# board.net
KiCad netlist of a schematic drawn in EAGLE
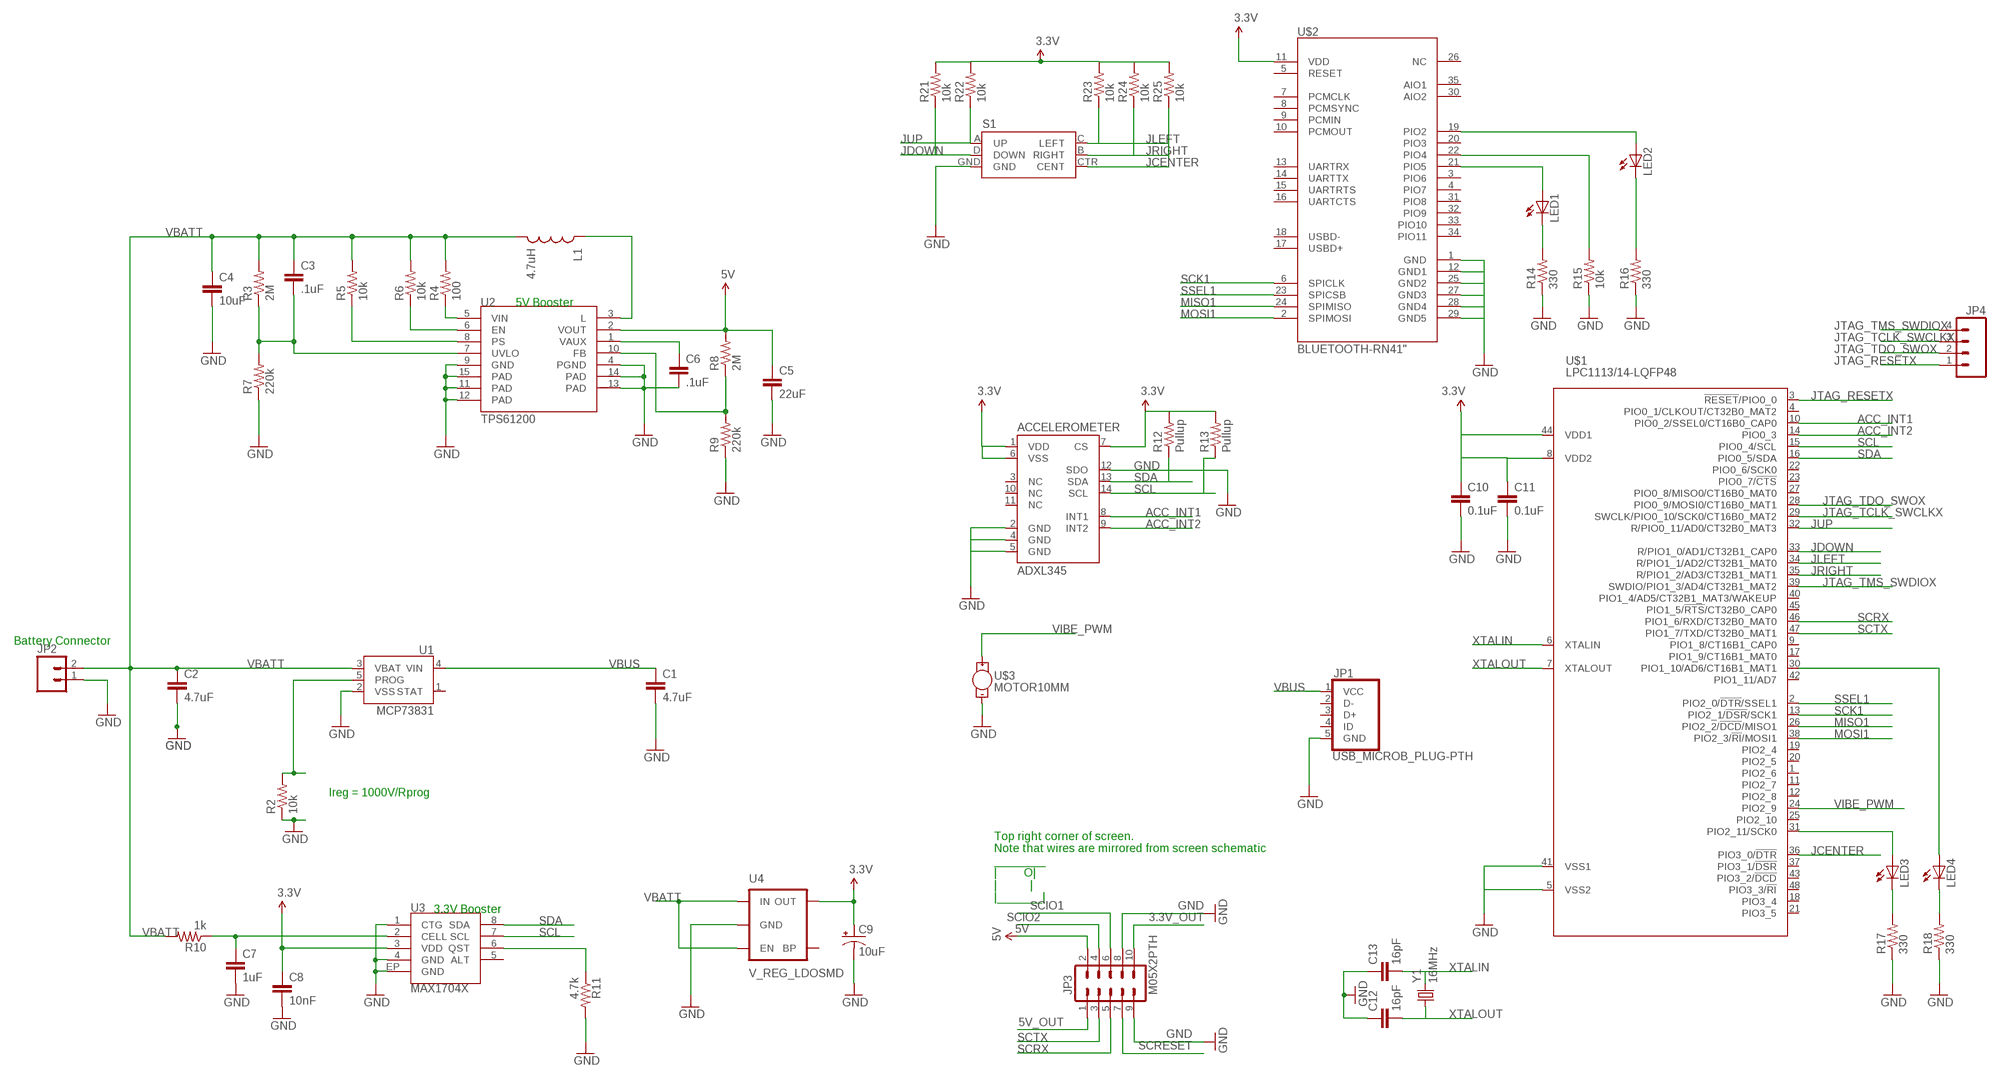
[diagram p0: schematic, sheet 1]

(export (version "E")
  (design (tool "Eeschema 10.0.6"))
  (components
    (comp (ref "ACCELEROMETER")
      (value "ADXL345")
      (footprint "eagle-import:LGA14")
      (libsource (lib "eagle-import") (part "ADXL345"))
    )
    (comp (ref "C1")
      (value "4.7uF")
      (footprint "eagle-import:0402-CAP")
      (libsource (lib "eagle-import") (part "CAP0402-CAP"))
    )
    (comp (ref "C2")
      (value "4.7uF")
      (footprint "eagle-import:0402-CAP")
      (libsource (lib "eagle-import") (part "CAP0402-CAP"))
    )
    (comp (ref "C3")
      (value ".1uF")
      (footprint "eagle-import:0402-CAP")
      (libsource (lib "eagle-import") (part "CAP0402-CAP"))
    )
    (comp (ref "C4")
      (value "10uF")
      (footprint "eagle-import:0402-CAP")
      (libsource (lib "eagle-import") (part "CAP0402-CAP"))
    )
    (comp (ref "C5")
      (value "22uF")
      (footprint "eagle-import:0402-CAP")
      (libsource (lib "eagle-import") (part "CAP0402-CAP"))
    )
    (comp (ref "C6")
      (value ".1uF")
      (footprint "eagle-import:0402-CAP")
      (libsource (lib "eagle-import") (part "CAP0402-CAP"))
    )
    (comp (ref "C7")
      (value "1uF")
      (footprint "eagle-import:0402-CAP")
      (libsource (lib "eagle-import") (part "CAP0402-CAP"))
    )
    (comp (ref "C8")
      (value "10nF")
      (footprint "eagle-import:0402-CAP")
      (libsource (lib "eagle-import") (part "CAP0402-CAP"))
    )
    (comp (ref "C9")
      (value "10uF")
      (footprint "eagle-import:EIA3216")
      (libsource (lib "eagle-import") (part "10UF-TANT"))
    )
    (comp (ref "C10")
      (value "0.1uF")
      (footprint "eagle-import:0402-CAP")
      (libsource (lib "eagle-import") (part ".1UF-CER"))
    )
    (comp (ref "C11")
      (value "0.1uF")
      (footprint "eagle-import:0402-CAP")
      (libsource (lib "eagle-import") (part ".1UF-CER"))
    )
    (comp (ref "C12")
      (value "16pF")
      (footprint "eagle-import:0402-CAP")
      (libsource (lib "eagle-import") (part "CAP0402-CAP"))
    )
    (comp (ref "C13")
      (value "16pF")
      (footprint "eagle-import:0402-CAP")
      (libsource (lib "eagle-import") (part "CAP0402-CAP"))
    )
    (comp (ref "JP1")
      (value "USB_MICROB_PLUG-PTH")
      (footprint "eagle-import:MICRO-B-RA-TH")
      (libsource (lib "eagle-import") (part "USB_MICROB_PLUG-PTH"))
    )
    (comp (ref "JP2")
      (value "M02-JST-2-PTH-NO_SILK")
      (footprint "eagle-import:JST-2-PTH-NS")
      (libsource (lib "eagle-import") (part "M02-JST-2-PTH-NO_SILK"))
    )
    (comp (ref "JP3")
      (value "M05X2PTH")
      (footprint "eagle-import:AVR_ICSP")
      (libsource (lib "eagle-import") (part "M05X2PTH"))
    )
    (comp (ref "JP4")
      (value "M04POLAR")
      (footprint "eagle-import:MOLEX-1X4")
      (libsource (lib "eagle-import") (part "M04POLAR"))
    )
    (comp (ref "L1")
      (value "4.7uH")
      (footprint "eagle-import:C0402")
      (libsource (lib "eagle-import") (part "INDUCTOR0402"))
    )
    (comp (ref "LED1")
      (value "LED0603")
      (footprint "eagle-import:LED-0603")
      (libsource (lib "eagle-import") (part "LED0603"))
    )
    (comp (ref "LED2")
      (value "LED0603")
      (footprint "eagle-import:LED-0603")
      (libsource (lib "eagle-import") (part "LED0603"))
    )
    (comp (ref "LED3")
      (value "LED0603")
      (footprint "eagle-import:LED-0603")
      (libsource (lib "eagle-import") (part "LED0603"))
    )
    (comp (ref "LED4")
      (value "LED0603")
      (footprint "eagle-import:LED-0603")
      (libsource (lib "eagle-import") (part "LED0603"))
    )
    (comp (ref "R2")
      (value "10k")
      (footprint "eagle-import:0402-RES")
      (libsource (lib "eagle-import") (part "RESISTOR0402-RES"))
    )
    (comp (ref "R3")
      (value "2M")
      (footprint "eagle-import:0402-RES")
      (libsource (lib "eagle-import") (part "RESISTOR0402-RES"))
    )
    (comp (ref "R4")
      (value "100")
      (footprint "eagle-import:0402-RES")
      (libsource (lib "eagle-import") (part "RESISTOR0402-RES"))
    )
    (comp (ref "R5")
      (value "10k")
      (footprint "eagle-import:0402-RES")
      (libsource (lib "eagle-import") (part "RESISTOR0402-RES"))
    )
    (comp (ref "R6")
      (value "10k")
      (footprint "eagle-import:0402-RES")
      (libsource (lib "eagle-import") (part "RESISTOR0402-RES"))
    )
    (comp (ref "R7")
      (value "220k")
      (footprint "eagle-import:0402-RES")
      (libsource (lib "eagle-import") (part "RESISTOR0402-RES"))
    )
    (comp (ref "R8")
      (value "2M")
      (footprint "eagle-import:0402-RES")
      (libsource (lib "eagle-import") (part "RESISTOR0402-RES"))
    )
    (comp (ref "R9")
      (value "220k")
      (footprint "eagle-import:0402-RES")
      (libsource (lib "eagle-import") (part "RESISTOR0402-RES"))
    )
    (comp (ref "R10")
      (value "1k")
      (footprint "eagle-import:0402-RES")
      (libsource (lib "eagle-import") (part "RESISTOR0402-RES"))
    )
    (comp (ref "R11")
      (value "4.7k")
      (footprint "eagle-import:0402-RES")
      (libsource (lib "eagle-import") (part "RESISTOR0402-RES"))
    )
    (comp (ref "R12")
      (value "Pullup")
      (footprint "eagle-import:0402-RES")
      (libsource (lib "eagle-import") (part "RESISTOR0402-RES"))
    )
    (comp (ref "R13")
      (value "Pullup")
      (footprint "eagle-import:0402-RES")
      (libsource (lib "eagle-import") (part "RESISTOR0402-RES"))
    )
    (comp (ref "R14")
      (value "330")
      (footprint "eagle-import:0402-RES")
      (libsource (lib "eagle-import") (part "RESISTOR0402-RES"))
    )
    (comp (ref "R15")
      (value "10k")
      (footprint "eagle-import:0402-RES")
      (libsource (lib "eagle-import") (part "RESISTOR0402-RES"))
    )
    (comp (ref "R16")
      (value "330")
      (footprint "eagle-import:0402-RES")
      (libsource (lib "eagle-import") (part "RESISTOR0402-RES"))
    )
    (comp (ref "R17")
      (value "330")
      (footprint "eagle-import:0402-RES")
      (libsource (lib "eagle-import") (part "RESISTOR0402-RES"))
    )
    (comp (ref "R18")
      (value "330")
      (footprint "eagle-import:0402-RES")
      (libsource (lib "eagle-import") (part "RESISTOR0402-RES"))
    )
    (comp (ref "R21")
      (value "10k")
      (footprint "eagle-import:0402-RES")
      (libsource (lib "eagle-import") (part "RESISTOR0402-RES"))
    )
    (comp (ref "R22")
      (value "10k")
      (footprint "eagle-import:0402-RES")
      (libsource (lib "eagle-import") (part "RESISTOR0402-RES"))
    )
    (comp (ref "R23")
      (value "10k")
      (footprint "eagle-import:0402-RES")
      (libsource (lib "eagle-import") (part "RESISTOR0402-RES"))
    )
    (comp (ref "R24")
      (value "10k")
      (footprint "eagle-import:0402-RES")
      (libsource (lib "eagle-import") (part "RESISTOR0402-RES"))
    )
    (comp (ref "R25")
      (value "10k")
      (footprint "eagle-import:0402-RES")
      (libsource (lib "eagle-import") (part "RESISTOR0402-RES"))
    )
    (comp (ref "S1")
      (value "JOYSTICK_MINI")
      (footprint "eagle-import:JOYSTICK_MINI")
      (libsource (lib "eagle-import") (part "JOYSTICK_MINI"))
    )
    (comp (ref "U$1")
      (value "LPC1113/14-LQFP48")
      (footprint "eagle-import:LQFP48")
      (libsource (lib "eagle-import") (part "LPC1113/14-LQFP48"))
    )
    (comp (ref "U$2")
      (value "BLUETOOTH-RN41\"")
      (footprint "eagle-import:RN41")
      (libsource (lib "eagle-import") (part "BLUETOOTH-RN41{dblquote}"))
    )
    (comp (ref "U$3")
      (value "MOTOR10MM")
      (footprint "eagle-import:VIBE-MOTOR-10MM")
      (libsource (lib "eagle-import") (part "MOTOR10MM"))
    )
    (comp (ref "U1")
      (value "MCP73831")
      (footprint "eagle-import:SOT23-5")
      (libsource (lib "eagle-import") (part "MCP73831"))
    )
    (comp (ref "U2")
      (value "TPS61200")
      (footprint "eagle-import:QFN-10_PAD")
      (libsource (lib "eagle-import") (part "TPS61200"))
    )
    (comp (ref "U3")
      (value "MAX1704X")
      (footprint "eagle-import:TDFN-8")
      (libsource (lib "eagle-import") (part "MAX1704X"))
    )
    (comp (ref "U4")
      (value "V_REG_LDOSMD")
      (footprint "eagle-import:SOT23-5")
      (libsource (lib "eagle-import") (part "V_REG_LDOSMD"))
    )
    (comp (ref "Y1")
      (value "16MHz")
      (footprint "eagle-import:CRYSTAL-SMD-5X3")
      (libsource (lib "eagle-import") (part "CRYSTAL5X3"))
    )
  )
  (nets
    (net (code "1") (name "/3.3V_OUT") (class "Default")
      (node (ref "JP3") (pin "10") (pinfunction "10_10") (pintype "passive"))
    )
    (net (code "2") (name "/5V_OUT") (class "Default")
      (node (ref "JP3") (pin "1") (pinfunction "1_1") (pintype "passive"))
    )
    (net (code "3") (name "/ACC_INT1") (class "Default")
      (node (ref "ACCELEROMETER") (pin "8") (pinfunction "INT1_8") (pintype "bidirectional"))
      (node (ref "U$1") (pin "10") (pinfunction "PIO0_2/SSEL0/CT16B0_CAP0_10") (pintype "bidirectional"))
    )
    (net (code "4") (name "/ACC_INT2") (class "Default")
      (node (ref "ACCELEROMETER") (pin "9") (pinfunction "INT2_9") (pintype "bidirectional"))
      (node (ref "U$1") (pin "14") (pinfunction "PIO0_3_14") (pintype "bidirectional"))
    )
    (net (code "5") (name "/JCENTER") (class "Default")
      (node (ref "R25") (pin "1") (pinfunction "1_1") (pintype "passive"))
      (node (ref "S1") (pin "CTR") (pinfunction "CENT_CTR") (pintype "bidirectional"))
      (node (ref "U$1") (pin "36") (pinfunction "PIO3_0/~{DTR}_36") (pintype "bidirectional"))
    )
    (net (code "6") (name "/JDOWN") (class "Default")
      (node (ref "R21") (pin "1") (pinfunction "1_1") (pintype "passive"))
      (node (ref "S1") (pin "D") (pinfunction "DOWN_D") (pintype "bidirectional"))
      (node (ref "U$1") (pin "33") (pinfunction "R/PIO1_0/AD1/CT32B1_CAP0_33") (pintype "bidirectional"))
    )
    (net (code "7") (name "/JLEFT") (class "Default")
      (node (ref "R23") (pin "1") (pinfunction "1_1") (pintype "passive"))
      (node (ref "S1") (pin "C") (pinfunction "LEFT_C") (pintype "bidirectional"))
      (node (ref "U$1") (pin "34") (pinfunction "R/PIO1_1/AD2/CT32B1_MAT0_34") (pintype "bidirectional"))
    )
    (net (code "8") (name "/JRIGHT") (class "Default")
      (node (ref "R24") (pin "1") (pinfunction "1_1") (pintype "passive"))
      (node (ref "S1") (pin "B") (pinfunction "RIGHT_B") (pintype "bidirectional"))
      (node (ref "U$1") (pin "35") (pinfunction "R/PIO1_2/AD3/CT32B1_MAT1_35") (pintype "bidirectional"))
    )
    (net (code "9") (name "/JTAG_RESETX") (class "Default")
      (node (ref "JP4") (pin "1") (pinfunction "1_1") (pintype "passive"))
      (node (ref "U$1") (pin "3") (pinfunction "~{RESET}/PIO0_0_3") (pintype "bidirectional"))
    )
    (net (code "10") (name "/JTAG_TCLK_SWCLKX") (class "Default")
      (node (ref "JP4") (pin "3") (pinfunction "3_3") (pintype "passive"))
      (node (ref "U$1") (pin "29") (pinfunction "SWCLK/PIO0_10/SCK0/CT16B0_MAT2_29") (pintype "bidirectional"))
    )
    (net (code "11") (name "/JTAG_TDO_SWOX") (class "Default")
      (node (ref "JP4") (pin "2") (pinfunction "2_2") (pintype "passive"))
      (node (ref "U$1") (pin "28") (pinfunction "PIO0_9/MOSI0/CT16B0_MAT1_28") (pintype "bidirectional"))
    )
    (net (code "12") (name "/JTAG_TMS_SWDIOX") (class "Default")
      (node (ref "JP4") (pin "4") (pinfunction "4_4") (pintype "passive"))
      (node (ref "U$1") (pin "39") (pinfunction "SWDIO/PIO1_3/AD4/CT32B1_MAT2_39") (pintype "bidirectional"))
    )
    (net (code "13") (name "/JUP") (class "Default")
      (node (ref "R22") (pin "1") (pinfunction "1_1") (pintype "passive"))
      (node (ref "S1") (pin "A") (pinfunction "UP_A") (pintype "bidirectional"))
      (node (ref "U$1") (pin "32") (pinfunction "R/PIO0_11/AD0/CT32B0_MAT3_32") (pintype "bidirectional"))
    )
    (net (code "14") (name "/MISO1") (class "Default")
      (node (ref "U$1") (pin "26") (pinfunction "PIO2_2/~{DCD}/MISO1_26") (pintype "bidirectional"))
      (node (ref "U$2") (pin "24") (pinfunction "SPIMISO_24") (pintype "bidirectional"))
    )
    (net (code "15") (name "/MOSI1") (class "Default")
      (node (ref "U$1") (pin "38") (pinfunction "PIO2_3/~{RI}/MOSI1_38") (pintype "bidirectional"))
      (node (ref "U$2") (pin "2") (pinfunction "SPIMOSI_2") (pintype "bidirectional"))
    )
    (net (code "16") (name "/SCIO1") (class "Default")
      (node (ref "JP3") (pin "6") (pinfunction "6_6") (pintype "passive"))
    )
    (net (code "17") (name "/SCIO2") (class "Default")
      (node (ref "JP3") (pin "4") (pinfunction "4_4") (pintype "passive"))
    )
    (net (code "18") (name "/SCK1") (class "Default")
      (node (ref "U$1") (pin "13") (pinfunction "PIO2_1/~{DSR}/SCK1_13") (pintype "bidirectional"))
      (node (ref "U$2") (pin "6") (pinfunction "SPICLK_6") (pintype "bidirectional"))
    )
    (net (code "19") (name "/SCL") (class "Default")
      (node (ref "ACCELEROMETER") (pin "14") (pinfunction "SCL_14") (pintype "bidirectional"))
      (node (ref "R13") (pin "1") (pinfunction "1_1") (pintype "passive"))
      (node (ref "U$1") (pin "15") (pinfunction "PIO0_4/SCL_15") (pintype "bidirectional"))
      (node (ref "U3") (pin "7") (pinfunction "SCL_7") (pintype "bidirectional"))
    )
    (net (code "20") (name "/SCRESET") (class "Default")
      (node (ref "JP3") (pin "7") (pinfunction "7_7") (pintype "passive"))
    )
    (net (code "21") (name "/SCRX") (class "Default")
      (node (ref "JP3") (pin "5") (pinfunction "5_5") (pintype "passive"))
      (node (ref "U$1") (pin "46") (pinfunction "PIO1_6/RXD/CT32B0_MAT0_46") (pintype "bidirectional"))
    )
    (net (code "22") (name "/SCTX") (class "Default")
      (node (ref "JP3") (pin "3") (pinfunction "3_3") (pintype "passive"))
      (node (ref "U$1") (pin "47") (pinfunction "PIO1_7/TXD/CT32B0_MAT1_47") (pintype "bidirectional"))
    )
    (net (code "23") (name "/SDA") (class "Default")
      (node (ref "ACCELEROMETER") (pin "13") (pinfunction "SDA_13") (pintype "bidirectional"))
      (node (ref "R12") (pin "1") (pinfunction "1_1") (pintype "passive"))
      (node (ref "U$1") (pin "16") (pinfunction "PIO0_5/SDA_16") (pintype "bidirectional"))
      (node (ref "U3") (pin "8") (pinfunction "SDA_8") (pintype "bidirectional"))
    )
    (net (code "24") (name "/SSEL1") (class "Default")
      (node (ref "U$1") (pin "2") (pinfunction "PIO2_0/~{DTR}/SSEL1_2") (pintype "bidirectional"))
      (node (ref "U$2") (pin "23") (pinfunction "SPICSB_23") (pintype "bidirectional"))
    )
    (net (code "25") (name "/VBATT") (class "Default")
      (node (ref "C2") (pin "1") (pinfunction "1_1") (pintype "passive"))
      (node (ref "C3") (pin "1") (pinfunction "1_1") (pintype "passive"))
      (node (ref "C4") (pin "1") (pinfunction "1_1") (pintype "passive"))
      (node (ref "JP2") (pin "2") (pinfunction "2_2") (pintype "passive"))
      (node (ref "L1") (pin "2") (pinfunction "2_2") (pintype "passive"))
      (node (ref "R10") (pin "2") (pinfunction "2_2") (pintype "passive"))
      (node (ref "R3") (pin "2") (pinfunction "2_2") (pintype "passive"))
      (node (ref "R4") (pin "2") (pinfunction "2_2") (pintype "passive"))
      (node (ref "R5") (pin "2") (pinfunction "2_2") (pintype "passive"))
      (node (ref "R6") (pin "2") (pinfunction "2_2") (pintype "passive"))
      (node (ref "U1") (pin "3") (pinfunction "VBAT_3") (pintype "power_in"))
      (node (ref "U4") (pin "1") (pinfunction "IN_1") (pintype "input"))
      (node (ref "U4") (pin "3") (pinfunction "EN_3") (pintype "input"))
    )
    (net (code "26") (name "/VBUS") (class "Default")
      (node (ref "C1") (pin "1") (pinfunction "1_1") (pintype "passive"))
      (node (ref "JP1") (pin "1") (pinfunction "VCC_1") (pintype "bidirectional"))
      (node (ref "U1") (pin "4") (pinfunction "VIN_4") (pintype "power_in"))
    )
    (net (code "27") (name "/VIBE_PWM") (class "Default")
      (node (ref "U$1") (pin "24") (pinfunction "PIO2_9_24") (pintype "bidirectional"))
      (node (ref "U$3") (pin "+") (pinfunction "+_+") (pintype "bidirectional"))
    )
    (net (code "28") (name "/XTALIN") (class "Default")
      (node (ref "C13") (pin "2") (pinfunction "2_2") (pintype "passive"))
      (node (ref "U$1") (pin "6") (pinfunction "XTALIN_6") (pintype "passive"))
      (node (ref "Y1") (pin "3") (pinfunction "2_3") (pintype "passive"))
    )
    (net (code "29") (name "/XTALOUT") (class "Default")
      (node (ref "C12") (pin "2") (pinfunction "2_2") (pintype "passive"))
      (node (ref "U$1") (pin "7") (pinfunction "XTALOUT_7") (pintype "passive"))
      (node (ref "Y1") (pin "1") (pinfunction "1_1") (pintype "passive"))
    )
    (net (code "30") (name "3.3V") (class "Default")
      (node (ref "ACCELEROMETER") (pin "1") (pinfunction "VDD_1") (pintype "bidirectional"))
      (node (ref "ACCELEROMETER") (pin "6") (pinfunction "VSS_6") (pintype "bidirectional"))
      (node (ref "ACCELEROMETER") (pin "7") (pinfunction "CS_7") (pintype "bidirectional"))
      (node (ref "C10") (pin "1") (pinfunction "1_1") (pintype "passive"))
      (node (ref "C11") (pin "1") (pinfunction "1_1") (pintype "passive"))
      (node (ref "C8") (pin "1") (pinfunction "1_1") (pintype "passive"))
      (node (ref "C9") (pin "A") (pinfunction "+_A") (pintype "passive"))
      (node (ref "R12") (pin "2") (pinfunction "2_2") (pintype "passive"))
      (node (ref "R13") (pin "2") (pinfunction "2_2") (pintype "passive"))
      (node (ref "R21") (pin "2") (pinfunction "2_2") (pintype "passive"))
      (node (ref "R22") (pin "2") (pinfunction "2_2") (pintype "passive"))
      (node (ref "R23") (pin "2") (pinfunction "2_2") (pintype "passive"))
      (node (ref "R24") (pin "2") (pinfunction "2_2") (pintype "passive"))
      (node (ref "R25") (pin "2") (pinfunction "2_2") (pintype "passive"))
      (node (ref "U$1") (pin "44") (pinfunction "VDD1_44") (pintype "power_in"))
      (node (ref "U$1") (pin "8") (pinfunction "VDD2_8") (pintype "power_in"))
      (node (ref "U$2") (pin "11") (pinfunction "VDD_11") (pintype "bidirectional"))
      (node (ref "U3") (pin "3") (pinfunction "VDD_3") (pintype "bidirectional"))
      (node (ref "U4") (pin "5") (pinfunction "OUT_5") (pintype "passive"))
    )
    (net (code "31") (name "5V") (class "Default")
      (node (ref "C5") (pin "1") (pinfunction "1_1") (pintype "passive"))
      (node (ref "JP3") (pin "2") (pinfunction "2_2") (pintype "passive"))
      (node (ref "R8") (pin "2") (pinfunction "2_2") (pintype "passive"))
      (node (ref "U2") (pin "2") (pinfunction "VOUT_2") (pintype "passive"))
    )
    (net (code "32") (name "GND") (class "Default")
      (node (ref "ACCELEROMETER") (pin "12") (pinfunction "SDO_12") (pintype "bidirectional"))
      (node (ref "ACCELEROMETER") (pin "2") (pinfunction "GND_2") (pintype "bidirectional"))
      (node (ref "ACCELEROMETER") (pin "4") (pinfunction "GND_4") (pintype "bidirectional"))
      (node (ref "ACCELEROMETER") (pin "5") (pinfunction "GND_5") (pintype "bidirectional"))
      (node (ref "C1") (pin "2") (pinfunction "2_2") (pintype "passive"))
      (node (ref "C10") (pin "2") (pinfunction "2_2") (pintype "passive"))
      (node (ref "C11") (pin "2") (pinfunction "2_2") (pintype "passive"))
      (node (ref "C12") (pin "1") (pinfunction "1_1") (pintype "passive"))
      (node (ref "C13") (pin "1") (pinfunction "1_1") (pintype "passive"))
      (node (ref "C2") (pin "2") (pinfunction "2_2") (pintype "passive"))
      (node (ref "C4") (pin "2") (pinfunction "2_2") (pintype "passive"))
      (node (ref "C5") (pin "2") (pinfunction "2_2") (pintype "passive"))
      (node (ref "C6") (pin "2") (pinfunction "2_2") (pintype "passive"))
      (node (ref "C7") (pin "2") (pinfunction "2_2") (pintype "passive"))
      (node (ref "C8") (pin "2") (pinfunction "2_2") (pintype "passive"))
      (node (ref "C9") (pin "C") (pinfunction "-_C") (pintype "passive"))
      (node (ref "JP1") (pin "5") (pinfunction "GND_5") (pintype "bidirectional"))
      (node (ref "JP2") (pin "1") (pinfunction "1_1") (pintype "passive"))
      (node (ref "JP3") (pin "8") (pinfunction "8_8") (pintype "passive"))
      (node (ref "JP3") (pin "9") (pinfunction "9_9") (pintype "passive"))
      (node (ref "R11") (pin "2") (pinfunction "2_2") (pintype "passive"))
      (node (ref "R14") (pin "1") (pinfunction "1_1") (pintype "passive"))
      (node (ref "R15") (pin "1") (pinfunction "1_1") (pintype "passive"))
      (node (ref "R16") (pin "1") (pinfunction "1_1") (pintype "passive"))
      (node (ref "R17") (pin "1") (pinfunction "1_1") (pintype "passive"))
      (node (ref "R18") (pin "1") (pinfunction "1_1") (pintype "passive"))
      (node (ref "R2") (pin "1") (pinfunction "1_1") (pintype "passive"))
      (node (ref "R7") (pin "1") (pinfunction "1_1") (pintype "passive"))
      (node (ref "R9") (pin "1") (pinfunction "1_1") (pintype "passive"))
      (node (ref "S1") (pin "GND") (pinfunction "GND_GND") (pintype "bidirectional"))
      (node (ref "U$1") (pin "41") (pinfunction "VSS1_41") (pintype "power_in"))
      (node (ref "U$1") (pin "5") (pinfunction "VSS2_5") (pintype "power_in"))
      (node (ref "U$2") (pin "1") (pinfunction "GND_1") (pintype "bidirectional"))
      (node (ref "U$2") (pin "12") (pinfunction "GND1_12") (pintype "bidirectional"))
      (node (ref "U$2") (pin "25") (pinfunction "GND2_25") (pintype "bidirectional"))
      (node (ref "U$2") (pin "27") (pinfunction "GND3_27") (pintype "bidirectional"))
      (node (ref "U$2") (pin "28") (pinfunction "GND4_28") (pintype "bidirectional"))
      (node (ref "U$2") (pin "29") (pinfunction "GND5_29") (pintype "bidirectional"))
      (node (ref "U$3") (pin "-") (pinfunction "-_-") (pintype "bidirectional"))
      (node (ref "U1") (pin "2") (pinfunction "VSS_2") (pintype "power_in"))
      (node (ref "U2") (pin "11") (pinfunction "PAD_11") (pintype "power_in"))
      (node (ref "U2") (pin "12") (pinfunction "PAD_12") (pintype "power_in"))
      (node (ref "U2") (pin "13") (pinfunction "PAD_13") (pintype "power_in"))
      (node (ref "U2") (pin "14") (pinfunction "PAD_14") (pintype "power_in"))
      (node (ref "U2") (pin "15") (pinfunction "PAD_15") (pintype "power_in"))
      (node (ref "U2") (pin "4") (pinfunction "PGND_4") (pintype "power_in"))
      (node (ref "U2") (pin "9") (pinfunction "GND_9") (pintype "power_in"))
      (node (ref "U3") (pin "1") (pinfunction "CTG_1") (pintype "bidirectional"))
      (node (ref "U3") (pin "4") (pinfunction "GND_4") (pintype "bidirectional"))
      (node (ref "U3") (pin "EP") (pinfunction "GND_EP") (pintype "bidirectional"))
      (node (ref "U4") (pin "2") (pinfunction "GND_2") (pintype "input"))
    )
    (net (code "33") (name "Net-(LED1-PadC)") (class "Default")
      (node (ref "LED1") (pin "C") (pinfunction "C_C") (pintype "passive"))
      (node (ref "R14") (pin "2") (pinfunction "2_2") (pintype "passive"))
    )
    (net (code "34") (name "Net-(LED2-PadC)") (class "Default")
      (node (ref "LED2") (pin "C") (pinfunction "C_C") (pintype "passive"))
      (node (ref "R16") (pin "2") (pinfunction "2_2") (pintype "passive"))
    )
    (net (code "35") (name "Net-(LED3-PadC)") (class "Default")
      (node (ref "LED3") (pin "C") (pinfunction "C_C") (pintype "passive"))
      (node (ref "R17") (pin "2") (pinfunction "2_2") (pintype "passive"))
    )
    (net (code "36") (name "Net-(LED4-PadC)") (class "Default")
      (node (ref "LED4") (pin "C") (pinfunction "C_C") (pintype "passive"))
      (node (ref "R18") (pin "2") (pinfunction "2_2") (pintype "passive"))
    )
    (net (code "37") (name "Net-(U$1-PIO1_10{slash}AD6{slash}CT16B1_MAT1)") (class "Default")
      (node (ref "LED4") (pin "A") (pinfunction "A_A") (pintype "passive"))
      (node (ref "U$1") (pin "30") (pinfunction "PIO1_10/AD6/CT16B1_MAT1_30") (pintype "bidirectional"))
    )
    (net (code "38") (name "Net-(U$1-PIO2_11{slash}SCK0)") (class "Default")
      (node (ref "LED3") (pin "A") (pinfunction "A_A") (pintype "passive"))
      (node (ref "U$1") (pin "31") (pinfunction "PIO2_11/SCK0_31") (pintype "bidirectional"))
    )
    (net (code "39") (name "Net-(U$2-PIO2)") (class "Default")
      (node (ref "LED2") (pin "A") (pinfunction "A_A") (pintype "passive"))
      (node (ref "U$2") (pin "19") (pinfunction "PIO2_19") (pintype "bidirectional"))
    )
    (net (code "40") (name "Net-(U$2-PIO4)") (class "Default")
      (node (ref "R15") (pin "2") (pinfunction "2_2") (pintype "passive"))
      (node (ref "U$2") (pin "22") (pinfunction "PIO4_22") (pintype "bidirectional"))
    )
    (net (code "41") (name "Net-(U$2-PIO5)") (class "Default")
      (node (ref "LED1") (pin "A") (pinfunction "A_A") (pintype "passive"))
      (node (ref "U$2") (pin "21") (pinfunction "PIO5_21") (pintype "bidirectional"))
    )
    (net (code "42") (name "Net-(U1-PROG)") (class "Default")
      (node (ref "R2") (pin "2") (pinfunction "2_2") (pintype "passive"))
      (node (ref "U1") (pin "5") (pinfunction "PROG_5") (pintype "input"))
    )
    (net (code "43") (name "Net-(U2-EN)") (class "Default")
      (node (ref "R6") (pin "1") (pinfunction "1_1") (pintype "passive"))
      (node (ref "U2") (pin "6") (pinfunction "EN_6") (pintype "input"))
    )
    (net (code "44") (name "Net-(U2-FB)") (class "Default")
      (node (ref "R8") (pin "1") (pinfunction "1_1") (pintype "passive"))
      (node (ref "R9") (pin "2") (pinfunction "2_2") (pintype "passive"))
      (node (ref "U2") (pin "10") (pinfunction "FB_10") (pintype "passive"))
    )
    (net (code "45") (name "Net-(U2-L)") (class "Default")
      (node (ref "L1") (pin "1") (pinfunction "1_1") (pintype "passive"))
      (node (ref "U2") (pin "3") (pinfunction "L_3") (pintype "passive"))
    )
    (net (code "46") (name "Net-(U2-PS)") (class "Default")
      (node (ref "R5") (pin "1") (pinfunction "1_1") (pintype "passive"))
      (node (ref "U2") (pin "8") (pinfunction "PS_8") (pintype "input"))
    )
    (net (code "47") (name "Net-(U2-UVLO)") (class "Default")
      (node (ref "C3") (pin "2") (pinfunction "2_2") (pintype "passive"))
      (node (ref "R3") (pin "1") (pinfunction "1_1") (pintype "passive"))
      (node (ref "R7") (pin "2") (pinfunction "2_2") (pintype "passive"))
      (node (ref "U2") (pin "7") (pinfunction "UVLO_7") (pintype "passive"))
    )
    (net (code "48") (name "Net-(U2-VAUX)") (class "Default")
      (node (ref "C6") (pin "1") (pinfunction "1_1") (pintype "passive"))
      (node (ref "U2") (pin "1") (pinfunction "VAUX_1") (pintype "passive"))
    )
    (net (code "49") (name "Net-(U2-VIN)") (class "Default")
      (node (ref "R4") (pin "1") (pinfunction "1_1") (pintype "passive"))
      (node (ref "U2") (pin "5") (pinfunction "VIN_5") (pintype "power_in"))
    )
    (net (code "50") (name "Net-(U3-CELL)") (class "Default")
      (node (ref "C7") (pin "1") (pinfunction "1_1") (pintype "passive"))
      (node (ref "R10") (pin "1") (pinfunction "1_1") (pintype "passive"))
      (node (ref "U3") (pin "2") (pinfunction "CELL_2") (pintype "bidirectional"))
    )
    (net (code "51") (name "Net-(U3-QST)") (class "Default")
      (node (ref "R11") (pin "1") (pinfunction "1_1") (pintype "passive"))
      (node (ref "U3") (pin "6") (pinfunction "QST_6") (pintype "bidirectional"))
    )
    (net (code "52") (name "unconnected-(ACCELEROMETER-NC-Pad3)") (class "Default")
      (node (ref "ACCELEROMETER") (pin "3") (pinfunction "NC_3") (pintype "bidirectional"))
    )
    (net (code "53") (name "unconnected-(ACCELEROMETER-NC-Pad10)") (class "Default")
      (node (ref "ACCELEROMETER") (pin "10") (pinfunction "NC_10") (pintype "bidirectional"))
    )
    (net (code "54") (name "unconnected-(ACCELEROMETER-NC-Pad11)") (class "Default")
      (node (ref "ACCELEROMETER") (pin "11") (pinfunction "NC_11") (pintype "bidirectional"))
    )
    (net (code "55") (name "unconnected-(JP1-D+-Pad3)") (class "Default")
      (node (ref "JP1") (pin "3") (pinfunction "D+_3") (pintype "bidirectional"))
    )
    (net (code "56") (name "unconnected-(JP1-D--Pad2)") (class "Default")
      (node (ref "JP1") (pin "2") (pinfunction "D-_2") (pintype "bidirectional"))
    )
    (net (code "57") (name "unconnected-(JP1-ID-Pad4)") (class "Default")
      (node (ref "JP1") (pin "4") (pinfunction "ID_4") (pintype "bidirectional"))
    )
    (net (code "58") (name "unconnected-(U$1-PIO0_1{slash}CLKOUT{slash}CT32B0_MAT2-Pad4)") (class "Default")
      (node (ref "U$1") (pin "4") (pinfunction "PIO0_1/CLKOUT/CT32B0_MAT2_4") (pintype "bidirectional"))
    )
    (net (code "59") (name "unconnected-(U$1-PIO0_6{slash}SCK0-Pad22)") (class "Default")
      (node (ref "U$1") (pin "22") (pinfunction "PIO0_6/SCK0_22") (pintype "bidirectional"))
    )
    (net (code "60") (name "unconnected-(U$1-PIO0_7{slash}~{CTS}-Pad23)") (class "Default")
      (node (ref "U$1") (pin "23") (pinfunction "PIO0_7/~{CTS}_23") (pintype "bidirectional"))
    )
    (net (code "61") (name "unconnected-(U$1-PIO0_8{slash}MISO0{slash}CT16B0_MAT0-Pad27)") (class "Default")
      (node (ref "U$1") (pin "27") (pinfunction "PIO0_8/MISO0/CT16B0_MAT0_27") (pintype "bidirectional"))
    )
    (net (code "62") (name "unconnected-(U$1-PIO1_4{slash}AD5{slash}CT32B1_MAT3{slash}WAKEUP-Pad40)") (class "Default")
      (node (ref "U$1") (pin "40") (pinfunction "PIO1_4/AD5/CT32B1_MAT3/WAKEUP_40") (pintype "bidirectional"))
    )
    (net (code "63") (name "unconnected-(U$1-PIO1_5{slash}~{RTS}{slash}CT32B0_CAP0-Pad45)") (class "Default")
      (node (ref "U$1") (pin "45") (pinfunction "PIO1_5/~{RTS}/CT32B0_CAP0_45") (pintype "bidirectional"))
    )
    (net (code "64") (name "unconnected-(U$1-PIO1_8{slash}CT16B1_CAP0-Pad9)") (class "Default")
      (node (ref "U$1") (pin "9") (pinfunction "PIO1_8/CT16B1_CAP0_9") (pintype "bidirectional"))
    )
    (net (code "65") (name "unconnected-(U$1-PIO1_9{slash}CT16B1_MAT0-Pad17)") (class "Default")
      (node (ref "U$1") (pin "17") (pinfunction "PIO1_9/CT16B1_MAT0_17") (pintype "bidirectional"))
    )
    (net (code "66") (name "unconnected-(U$1-PIO1_11{slash}AD7-Pad42)") (class "Default")
      (node (ref "U$1") (pin "42") (pinfunction "PIO1_11/AD7_42") (pintype "bidirectional"))
    )
    (net (code "67") (name "unconnected-(U$1-PIO2_4-Pad19)") (class "Default")
      (node (ref "U$1") (pin "19") (pinfunction "PIO2_4_19") (pintype "bidirectional"))
    )
    (net (code "68") (name "unconnected-(U$1-PIO2_5-Pad20)") (class "Default")
      (node (ref "U$1") (pin "20") (pinfunction "PIO2_5_20") (pintype "bidirectional"))
    )
    (net (code "69") (name "unconnected-(U$1-PIO2_6-Pad1)") (class "Default")
      (node (ref "U$1") (pin "1") (pinfunction "PIO2_6_1") (pintype "bidirectional"))
    )
    (net (code "70") (name "unconnected-(U$1-PIO2_7-Pad11)") (class "Default")
      (node (ref "U$1") (pin "11") (pinfunction "PIO2_7_11") (pintype "bidirectional"))
    )
    (net (code "71") (name "unconnected-(U$1-PIO2_8-Pad12)") (class "Default")
      (node (ref "U$1") (pin "12") (pinfunction "PIO2_8_12") (pintype "bidirectional"))
    )
    (net (code "72") (name "unconnected-(U$1-PIO2_10-Pad25)") (class "Default")
      (node (ref "U$1") (pin "25") (pinfunction "PIO2_10_25") (pintype "bidirectional"))
    )
    (net (code "73") (name "unconnected-(U$1-PIO3_1{slash}~{DSR}-Pad37)") (class "Default")
      (node (ref "U$1") (pin "37") (pinfunction "PIO3_1/~{DSR}_37") (pintype "bidirectional"))
    )
    (net (code "74") (name "unconnected-(U$1-PIO3_2{slash}~{DCD}-Pad43)") (class "Default")
      (node (ref "U$1") (pin "43") (pinfunction "PIO3_2/~{DCD}_43") (pintype "bidirectional"))
    )
    (net (code "75") (name "unconnected-(U$1-PIO3_3{slash}~{RI}-Pad48)") (class "Default")
      (node (ref "U$1") (pin "48") (pinfunction "PIO3_3/~{RI}_48") (pintype "bidirectional"))
    )
    (net (code "76") (name "unconnected-(U$1-PIO3_4-Pad18)") (class "Default")
      (node (ref "U$1") (pin "18") (pinfunction "PIO3_4_18") (pintype "bidirectional"))
    )
    (net (code "77") (name "unconnected-(U$1-PIO3_5-Pad21)") (class "Default")
      (node (ref "U$1") (pin "21") (pinfunction "PIO3_5_21") (pintype "bidirectional"))
    )
    (net (code "78") (name "unconnected-(U$2-AIO1-Pad35)") (class "Default")
      (node (ref "U$2") (pin "35") (pinfunction "AIO1_35") (pintype "bidirectional"))
    )
    (net (code "79") (name "unconnected-(U$2-AIO2-Pad30)") (class "Default")
      (node (ref "U$2") (pin "30") (pinfunction "AIO2_30") (pintype "bidirectional"))
    )
    (net (code "80") (name "unconnected-(U$2-NC-Pad26)") (class "Default")
      (node (ref "U$2") (pin "26") (pinfunction "NC_26") (pintype "bidirectional"))
    )
    (net (code "81") (name "unconnected-(U$2-PCMCLK-Pad7)") (class "Default")
      (node (ref "U$2") (pin "7") (pinfunction "PCMCLK_7") (pintype "bidirectional"))
    )
    (net (code "82") (name "unconnected-(U$2-PCMIN-Pad9)") (class "Default")
      (node (ref "U$2") (pin "9") (pinfunction "PCMIN_9") (pintype "bidirectional"))
    )
    (net (code "83") (name "unconnected-(U$2-PCMOUT-Pad10)") (class "Default")
      (node (ref "U$2") (pin "10") (pinfunction "PCMOUT_10") (pintype "bidirectional"))
    )
    (net (code "84") (name "unconnected-(U$2-PCMSYNC-Pad8)") (class "Default")
      (node (ref "U$2") (pin "8") (pinfunction "PCMSYNC_8") (pintype "bidirectional"))
    )
    (net (code "85") (name "unconnected-(U$2-PIO3-Pad20)") (class "Default")
      (node (ref "U$2") (pin "20") (pinfunction "PIO3_20") (pintype "bidirectional"))
    )
    (net (code "86") (name "unconnected-(U$2-PIO6-Pad3)") (class "Default")
      (node (ref "U$2") (pin "3") (pinfunction "PIO6_3") (pintype "bidirectional"))
    )
    (net (code "87") (name "unconnected-(U$2-PIO7-Pad4)") (class "Default")
      (node (ref "U$2") (pin "4") (pinfunction "PIO7_4") (pintype "bidirectional"))
    )
    (net (code "88") (name "unconnected-(U$2-PIO8-Pad31)") (class "Default")
      (node (ref "U$2") (pin "31") (pinfunction "PIO8_31") (pintype "bidirectional"))
    )
    (net (code "89") (name "unconnected-(U$2-PIO9-Pad32)") (class "Default")
      (node (ref "U$2") (pin "32") (pinfunction "PIO9_32") (pintype "bidirectional"))
    )
    (net (code "90") (name "unconnected-(U$2-PIO10-Pad33)") (class "Default")
      (node (ref "U$2") (pin "33") (pinfunction "PIO10_33") (pintype "bidirectional"))
    )
    (net (code "91") (name "unconnected-(U$2-PIO11-Pad34)") (class "Default")
      (node (ref "U$2") (pin "34") (pinfunction "PIO11_34") (pintype "bidirectional"))
    )
    (net (code "92") (name "unconnected-(U$2-RESET-Pad5)") (class "Default")
      (node (ref "U$2") (pin "5") (pinfunction "RESET_5") (pintype "bidirectional"))
    )
    (net (code "93") (name "unconnected-(U$2-UARTCTS-Pad16)") (class "Default")
      (node (ref "U$2") (pin "16") (pinfunction "UARTCTS_16") (pintype "bidirectional"))
    )
    (net (code "94") (name "unconnected-(U$2-UARTRTS-Pad15)") (class "Default")
      (node (ref "U$2") (pin "15") (pinfunction "UARTRTS_15") (pintype "bidirectional"))
    )
    (net (code "95") (name "unconnected-(U$2-UARTRX-Pad13)") (class "Default")
      (node (ref "U$2") (pin "13") (pinfunction "UARTRX_13") (pintype "bidirectional"))
    )
    (net (code "96") (name "unconnected-(U$2-UARTTX-Pad14)") (class "Default")
      (node (ref "U$2") (pin "14") (pinfunction "UARTTX_14") (pintype "bidirectional"))
    )
    (net (code "97") (name "unconnected-(U$2-USBD+-Pad17)") (class "Default")
      (node (ref "U$2") (pin "17") (pinfunction "USBD+_17") (pintype "bidirectional"))
    )
    (net (code "98") (name "unconnected-(U$2-USBD--Pad18)") (class "Default")
      (node (ref "U$2") (pin "18") (pinfunction "USBD-_18") (pintype "bidirectional"))
    )
    (net (code "99") (name "unconnected-(U1-STAT-Pad1)") (class "Default")
      (node (ref "U1") (pin "1") (pinfunction "STAT_1") (pintype "output"))
    )
    (net (code "100") (name "unconnected-(U3-ALT-Pad5)") (class "Default")
      (node (ref "U3") (pin "5") (pinfunction "ALT_5") (pintype "bidirectional"))
    )
    (net (code "101") (name "unconnected-(U4-BP-Pad4)") (class "Default")
      (node (ref "U4") (pin "4") (pinfunction "BP_4") (pintype "input"))
    )
  )
)
